# untitled.net
KiCad netlist of a schematic drawn in EAGLE
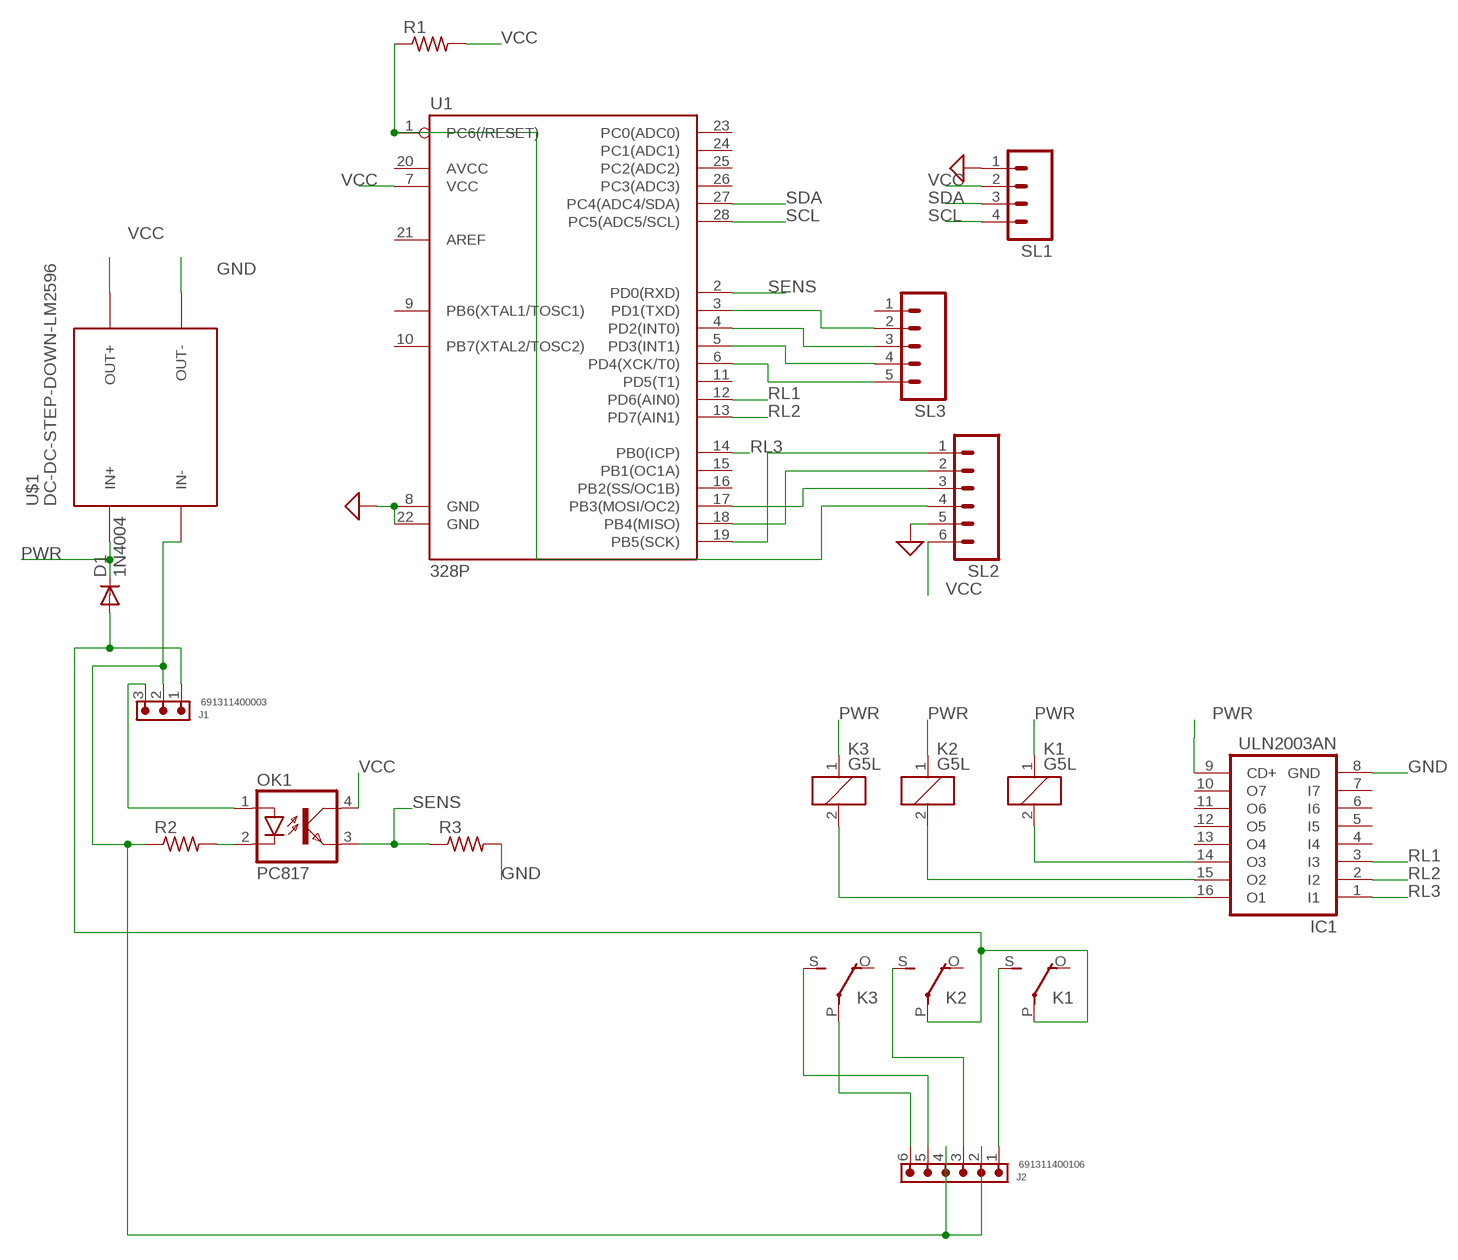
[diagram p0: schematic, sheet 1]

(export (version "E")
  (design (tool "Eeschema 10.0.6"))
  (components
    (comp (ref "D1")
      (value "1N4004")
      (footprint "eagle-import:DO41-10")
      (libsource (lib "eagle-import") (part "1N4004"))
    )
    (comp (ref "IC1")
      (value "ULN2003AN")
      (footprint "eagle-import:DIL16")
      (libsource (lib "eagle-import") (part "ULN2003AN"))
    )
    (comp (ref "J1")
      (value "691311400003")
      (footprint "eagle-import:691311400003")
      (libsource (lib "eagle-import") (part "691311400003"))
    )
    (comp (ref "J2")
      (value "691311400106")
      (footprint "eagle-import:691311400106")
      (libsource (lib "eagle-import") (part "691311400106"))
    )
    (comp (ref "K1")
      (value "G5L")
      (footprint "eagle-import:G5LE")
      (libsource (lib "eagle-import") (part "G5L"))
    )
    (comp (ref "K2")
      (value "G5L")
      (footprint "eagle-import:G5LE")
      (libsource (lib "eagle-import") (part "G5L"))
    )
    (comp (ref "K3")
      (value "G5L")
      (footprint "eagle-import:G5LE")
      (libsource (lib "eagle-import") (part "G5L"))
    )
    (comp (ref "OK1")
      (value "PC817")
      (footprint "eagle-import:DIL04")
      (fields (field (name "MPN") "PC817X4J000F"))
      (libsource (lib "eagle-import") (part "PC817"))
    )
    (comp (ref "R1")
      (value "R-US_0207/7")
      (footprint "eagle-import:0207_7")
      (libsource (lib "eagle-import") (part "R-US_0207/7"))
    )
    (comp (ref "R2")
      (value "R-US_0207/7")
      (footprint "eagle-import:0207_7")
      (libsource (lib "eagle-import") (part "R-US_0207/7"))
    )
    (comp (ref "R3")
      (value "R-US_0207/7")
      (footprint "eagle-import:0207_7")
      (libsource (lib "eagle-import") (part "R-US_0207/7"))
    )
    (comp (ref "SL1")
      (value "M04")
      (footprint "eagle-import:04P")
      (libsource (lib "eagle-import") (part "M04"))
    )
    (comp (ref "SL2")
      (value "M06")
      (footprint "eagle-import:06P")
      (libsource (lib "eagle-import") (part "M06"))
    )
    (comp (ref "SL3")
      (value "M05")
      (footprint "eagle-import:05P")
      (libsource (lib "eagle-import") (part "M05"))
    )
    (comp (ref "U$1")
      (value "DC-DC-STEP-DOWN-LM2596")
      (footprint "eagle-import:DC-DC-STEP-DOWN-LM2596")
      (libsource (lib "eagle-import") (part "DC-DC-STEP-DOWN-LM2596"))
    )
    (comp (ref "U1")
      (value "328P")
      (footprint "eagle-import:DIP28")
      (libsource (lib "eagle-import") (part "ATMEGA328P_PDIP"))
    )
  )
  (nets
    (net (code "1") (name "/PWR") (class "Default")
      (node (ref "D1") (pin "C") (pinfunction "C_C") (pintype "passive"))
      (node (ref "IC1") (pin "9") (pinfunction "CD+_9") (pintype "passive"))
      (node (ref "K1") (pin "1") (pinfunction "1_1") (pintype "passive"))
      (node (ref "K2") (pin "1") (pinfunction "1_1") (pintype "passive"))
      (node (ref "K3") (pin "1") (pinfunction "1_1") (pintype "passive"))
      (node (ref "U$1") (pin "IN+") (pinfunction "IN+_IN+") (pintype "bidirectional"))
    )
    (net (code "2") (name "/RL1") (class "Default")
      (node (ref "IC1") (pin "3") (pinfunction "I3_3") (pintype "input"))
      (node (ref "U1") (pin "12") (pinfunction "PD6(AIN0)_12") (pintype "bidirectional"))
    )
    (net (code "3") (name "/RL2") (class "Default")
      (node (ref "IC1") (pin "2") (pinfunction "I2_2") (pintype "input"))
      (node (ref "U1") (pin "13") (pinfunction "PD7(AIN1)_13") (pintype "bidirectional"))
    )
    (net (code "4") (name "/RL3") (class "Default")
      (node (ref "IC1") (pin "1") (pinfunction "I1_1") (pintype "input"))
      (node (ref "U1") (pin "14") (pinfunction "PB0(ICP)_14") (pintype "bidirectional"))
    )
    (net (code "5") (name "/SCL") (class "Default")
      (node (ref "SL1") (pin "4") (pinfunction "4_4") (pintype "passive"))
      (node (ref "U1") (pin "28") (pinfunction "PC5(ADC5/SCL)_28") (pintype "bidirectional"))
    )
    (net (code "6") (name "/SDA") (class "Default")
      (node (ref "SL1") (pin "3") (pinfunction "3_3") (pintype "passive"))
      (node (ref "U1") (pin "27") (pinfunction "PC4(ADC4/SDA)_27") (pintype "bidirectional"))
    )
    (net (code "7") (name "/SENS") (class "Default")
      (node (ref "OK1") (pin "3") (pinfunction "EMIT_3") (pintype "passive"))
      (node (ref "R3") (pin "1") (pinfunction "1_1") (pintype "passive"))
      (node (ref "U1") (pin "2") (pinfunction "PD0(RXD)_2") (pintype "bidirectional"))
    )
    (net (code "8") (name "/VCC") (class "Default")
      (node (ref "OK1") (pin "4") (pinfunction "COL_4") (pintype "passive"))
      (node (ref "R1") (pin "2") (pinfunction "2_2") (pintype "passive"))
      (node (ref "SL1") (pin "2") (pinfunction "2_2") (pintype "passive"))
      (node (ref "SL2") (pin "6") (pinfunction "6_6") (pintype "passive"))
      (node (ref "U$1") (pin "OUT+") (pinfunction "OUT+_OUT+") (pintype "bidirectional"))
      (node (ref "U1") (pin "7") (pinfunction "VCC_7") (pintype "bidirectional"))
    )
    (net (code "9") (name "Net-(D1-PadA)") (class "Default")
      (node (ref "D1") (pin "A") (pinfunction "A_A") (pintype "passive"))
      (node (ref "J1") (pin "1") (pinfunction "1_1") (pintype "passive"))
      (node (ref "K1") (pin "P") (pinfunction "P_P") (pintype "passive"))
      (node (ref "K2") (pin "P") (pinfunction "P_P") (pintype "passive"))
    )
    (net (code "10") (name "Net-(IC1-O1)") (class "Default")
      (node (ref "IC1") (pin "16") (pinfunction "O1_16") (pintype "open_collector"))
      (node (ref "K3") (pin "2") (pinfunction "2_2") (pintype "passive"))
    )
    (net (code "11") (name "Net-(IC1-O2)") (class "Default")
      (node (ref "IC1") (pin "15") (pinfunction "O2_15") (pintype "open_collector"))
      (node (ref "K2") (pin "2") (pinfunction "2_2") (pintype "passive"))
    )
    (net (code "12") (name "Net-(IC1-O3)") (class "Default")
      (node (ref "IC1") (pin "14") (pinfunction "O3_14") (pintype "open_collector"))
      (node (ref "K1") (pin "2") (pinfunction "2_2") (pintype "passive"))
    )
    (net (code "13") (name "Net-(J1-Pad2)") (class "Default")
      (node (ref "J1") (pin "2") (pinfunction "2_2") (pintype "passive"))
      (node (ref "J2") (pin "2") (pinfunction "2_2") (pintype "passive"))
      (node (ref "J2") (pin "4") (pinfunction "4_4") (pintype "passive"))
      (node (ref "R2") (pin "1") (pinfunction "1_1") (pintype "passive"))
      (node (ref "U$1") (pin "IN-") (pinfunction "IN-_IN-") (pintype "bidirectional"))
    )
    (net (code "14") (name "Net-(J2-Pad1)") (class "Default")
      (node (ref "J2") (pin "1") (pinfunction "1_1") (pintype "passive"))
      (node (ref "K1") (pin "S") (pinfunction "S_S") (pintype "passive"))
    )
    (net (code "15") (name "Net-(J2-Pad3)") (class "Default")
      (node (ref "J2") (pin "3") (pinfunction "3_3") (pintype "passive"))
      (node (ref "K2") (pin "S") (pinfunction "S_S") (pintype "passive"))
    )
    (net (code "16") (name "Net-(J2-Pad5)") (class "Default")
      (node (ref "J2") (pin "5") (pinfunction "5_5") (pintype "passive"))
      (node (ref "K3") (pin "S") (pinfunction "S_S") (pintype "passive"))
    )
    (net (code "17") (name "Net-(J2-Pad6)") (class "Default")
      (node (ref "J2") (pin "6") (pinfunction "6_6") (pintype "passive"))
      (node (ref "K3") (pin "P") (pinfunction "P_P") (pintype "passive"))
    )
    (net (code "18") (name "Net-(OK1-A)") (class "Default")
      (node (ref "J1") (pin "3") (pinfunction "3_3") (pintype "passive"))
      (node (ref "OK1") (pin "1") (pinfunction "A_1") (pintype "passive"))
    )
    (net (code "19") (name "Net-(OK1-C)") (class "Default")
      (node (ref "OK1") (pin "2") (pinfunction "C_2") (pintype "passive"))
      (node (ref "R2") (pin "2") (pinfunction "2_2") (pintype "passive"))
    )
    (net (code "20") (name "Net-(U1-PB3(MOSI{slash}OC2))") (class "Default")
      (node (ref "SL2") (pin "3") (pinfunction "3_3") (pintype "passive"))
      (node (ref "U1") (pin "17") (pinfunction "PB3(MOSI/OC2)_17") (pintype "bidirectional"))
    )
    (net (code "21") (name "Net-(U1-PB4(MISO))") (class "Default")
      (node (ref "SL2") (pin "2") (pinfunction "2_2") (pintype "passive"))
      (node (ref "U1") (pin "18") (pinfunction "PB4(MISO)_18") (pintype "bidirectional"))
    )
    (net (code "22") (name "Net-(U1-PB5(SCK))") (class "Default")
      (node (ref "SL2") (pin "1") (pinfunction "1_1") (pintype "passive"))
      (node (ref "U1") (pin "19") (pinfunction "PB5(SCK)_19") (pintype "bidirectional"))
    )
    (net (code "23") (name "Net-(U1-PC6({slash}RESET))") (class "Default")
      (node (ref "R1") (pin "1") (pinfunction "1_1") (pintype "passive"))
      (node (ref "SL2") (pin "4") (pinfunction "4_4") (pintype "passive"))
      (node (ref "U1") (pin "1") (pinfunction "PC6(/RESET)_1") (pintype "bidirectional"))
    )
    (net (code "24") (name "Net-(U1-PD1(TXD))") (class "Default")
      (node (ref "SL3") (pin "2") (pinfunction "2_2") (pintype "passive"))
      (node (ref "U1") (pin "3") (pinfunction "PD1(TXD)_3") (pintype "bidirectional"))
    )
    (net (code "25") (name "Net-(U1-PD2(INT0))") (class "Default")
      (node (ref "SL3") (pin "3") (pinfunction "3_3") (pintype "passive"))
      (node (ref "U1") (pin "4") (pinfunction "PD2(INT0)_4") (pintype "bidirectional"))
    )
    (net (code "26") (name "Net-(U1-PD3(INT1))") (class "Default")
      (node (ref "SL3") (pin "4") (pinfunction "4_4") (pintype "passive"))
      (node (ref "U1") (pin "5") (pinfunction "PD3(INT1)_5") (pintype "bidirectional"))
    )
    (net (code "27") (name "Net-(U1-PD4(XCK{slash}T0))") (class "Default")
      (node (ref "SL3") (pin "5") (pinfunction "5_5") (pintype "passive"))
      (node (ref "U1") (pin "6") (pinfunction "PD4(XCK/T0)_6") (pintype "bidirectional"))
    )
    (net (code "28") (name "SUP") (class "Default")
      (node (ref "IC1") (pin "8") (pinfunction "GND_8") (pintype "power_in"))
      (node (ref "R3") (pin "2") (pinfunction "2_2") (pintype "passive"))
      (node (ref "SL1") (pin "1") (pinfunction "1_1") (pintype "passive"))
      (node (ref "SL2") (pin "5") (pinfunction "5_5") (pintype "passive"))
      (node (ref "U$1") (pin "OUT-") (pinfunction "OUT-_OUT-") (pintype "bidirectional"))
      (node (ref "U1") (pin "22") (pinfunction "GND_22") (pintype "bidirectional"))
      (node (ref "U1") (pin "8") (pinfunction "GND_8") (pintype "bidirectional"))
    )
    (net (code "29") (name "unconnected-(IC1-I4-Pad4)") (class "Default")
      (node (ref "IC1") (pin "4") (pinfunction "I4_4") (pintype "input"))
    )
    (net (code "30") (name "unconnected-(IC1-I5-Pad5)") (class "Default")
      (node (ref "IC1") (pin "5") (pinfunction "I5_5") (pintype "input"))
    )
    (net (code "31") (name "unconnected-(IC1-I6-Pad6)") (class "Default")
      (node (ref "IC1") (pin "6") (pinfunction "I6_6") (pintype "input"))
    )
    (net (code "32") (name "unconnected-(IC1-I7-Pad7)") (class "Default")
      (node (ref "IC1") (pin "7") (pinfunction "I7_7") (pintype "input"))
    )
    (net (code "33") (name "unconnected-(IC1-O4-Pad13)") (class "Default")
      (node (ref "IC1") (pin "13") (pinfunction "O4_13") (pintype "open_collector"))
    )
    (net (code "34") (name "unconnected-(IC1-O5-Pad12)") (class "Default")
      (node (ref "IC1") (pin "12") (pinfunction "O5_12") (pintype "open_collector"))
    )
    (net (code "35") (name "unconnected-(IC1-O6-Pad11)") (class "Default")
      (node (ref "IC1") (pin "11") (pinfunction "O6_11") (pintype "open_collector"))
    )
    (net (code "36") (name "unconnected-(IC1-O7-Pad10)") (class "Default")
      (node (ref "IC1") (pin "10") (pinfunction "O7_10") (pintype "open_collector"))
    )
    (net (code "37") (name "unconnected-(K1-PadO)") (class "Default")
      (node (ref "K1") (pin "O") (pinfunction "O_O") (pintype "passive"))
    )
    (net (code "38") (name "unconnected-(K2-PadO)") (class "Default")
      (node (ref "K2") (pin "O") (pinfunction "O_O") (pintype "passive"))
    )
    (net (code "39") (name "unconnected-(K3-PadO)") (class "Default")
      (node (ref "K3") (pin "O") (pinfunction "O_O") (pintype "passive"))
    )
    (net (code "40") (name "unconnected-(SL3-Pad1)") (class "Default")
      (node (ref "SL3") (pin "1") (pinfunction "1_1") (pintype "passive"))
    )
    (net (code "41") (name "unconnected-(U1-AREF-Pad21)") (class "Default")
      (node (ref "U1") (pin "21") (pinfunction "AREF_21") (pintype "bidirectional"))
    )
    (net (code "42") (name "unconnected-(U1-AVCC-Pad20)") (class "Default")
      (node (ref "U1") (pin "20") (pinfunction "AVCC_20") (pintype "bidirectional"))
    )
    (net (code "43") (name "unconnected-(U1-PB1(OC1A)-Pad15)") (class "Default")
      (node (ref "U1") (pin "15") (pinfunction "PB1(OC1A)_15") (pintype "bidirectional"))
    )
    (net (code "44") (name "unconnected-(U1-PB2(SS{slash}OC1B)-Pad16)") (class "Default")
      (node (ref "U1") (pin "16") (pinfunction "PB2(SS/OC1B)_16") (pintype "bidirectional"))
    )
    (net (code "45") (name "unconnected-(U1-PB6(XTAL1{slash}TOSC1)-Pad9)") (class "Default")
      (node (ref "U1") (pin "9") (pinfunction "PB6(XTAL1/TOSC1)_9") (pintype "bidirectional"))
    )
    (net (code "46") (name "unconnected-(U1-PB7(XTAL2{slash}TOSC2)-Pad10)") (class "Default")
      (node (ref "U1") (pin "10") (pinfunction "PB7(XTAL2/TOSC2)_10") (pintype "bidirectional"))
    )
    (net (code "47") (name "unconnected-(U1-PC0(ADC0)-Pad23)") (class "Default")
      (node (ref "U1") (pin "23") (pinfunction "PC0(ADC0)_23") (pintype "bidirectional"))
    )
    (net (code "48") (name "unconnected-(U1-PC1(ADC1)-Pad24)") (class "Default")
      (node (ref "U1") (pin "24") (pinfunction "PC1(ADC1)_24") (pintype "bidirectional"))
    )
    (net (code "49") (name "unconnected-(U1-PC2(ADC2)-Pad25)") (class "Default")
      (node (ref "U1") (pin "25") (pinfunction "PC2(ADC2)_25") (pintype "bidirectional"))
    )
    (net (code "50") (name "unconnected-(U1-PC3(ADC3)-Pad26)") (class "Default")
      (node (ref "U1") (pin "26") (pinfunction "PC3(ADC3)_26") (pintype "bidirectional"))
    )
    (net (code "51") (name "unconnected-(U1-PD5(T1)-Pad11)") (class "Default")
      (node (ref "U1") (pin "11") (pinfunction "PD5(T1)_11") (pintype "bidirectional"))
    )
  )
)
